# Sheet_esp32_OPTO.net
KiCad netlist of a schematic drawn in Altium Designer
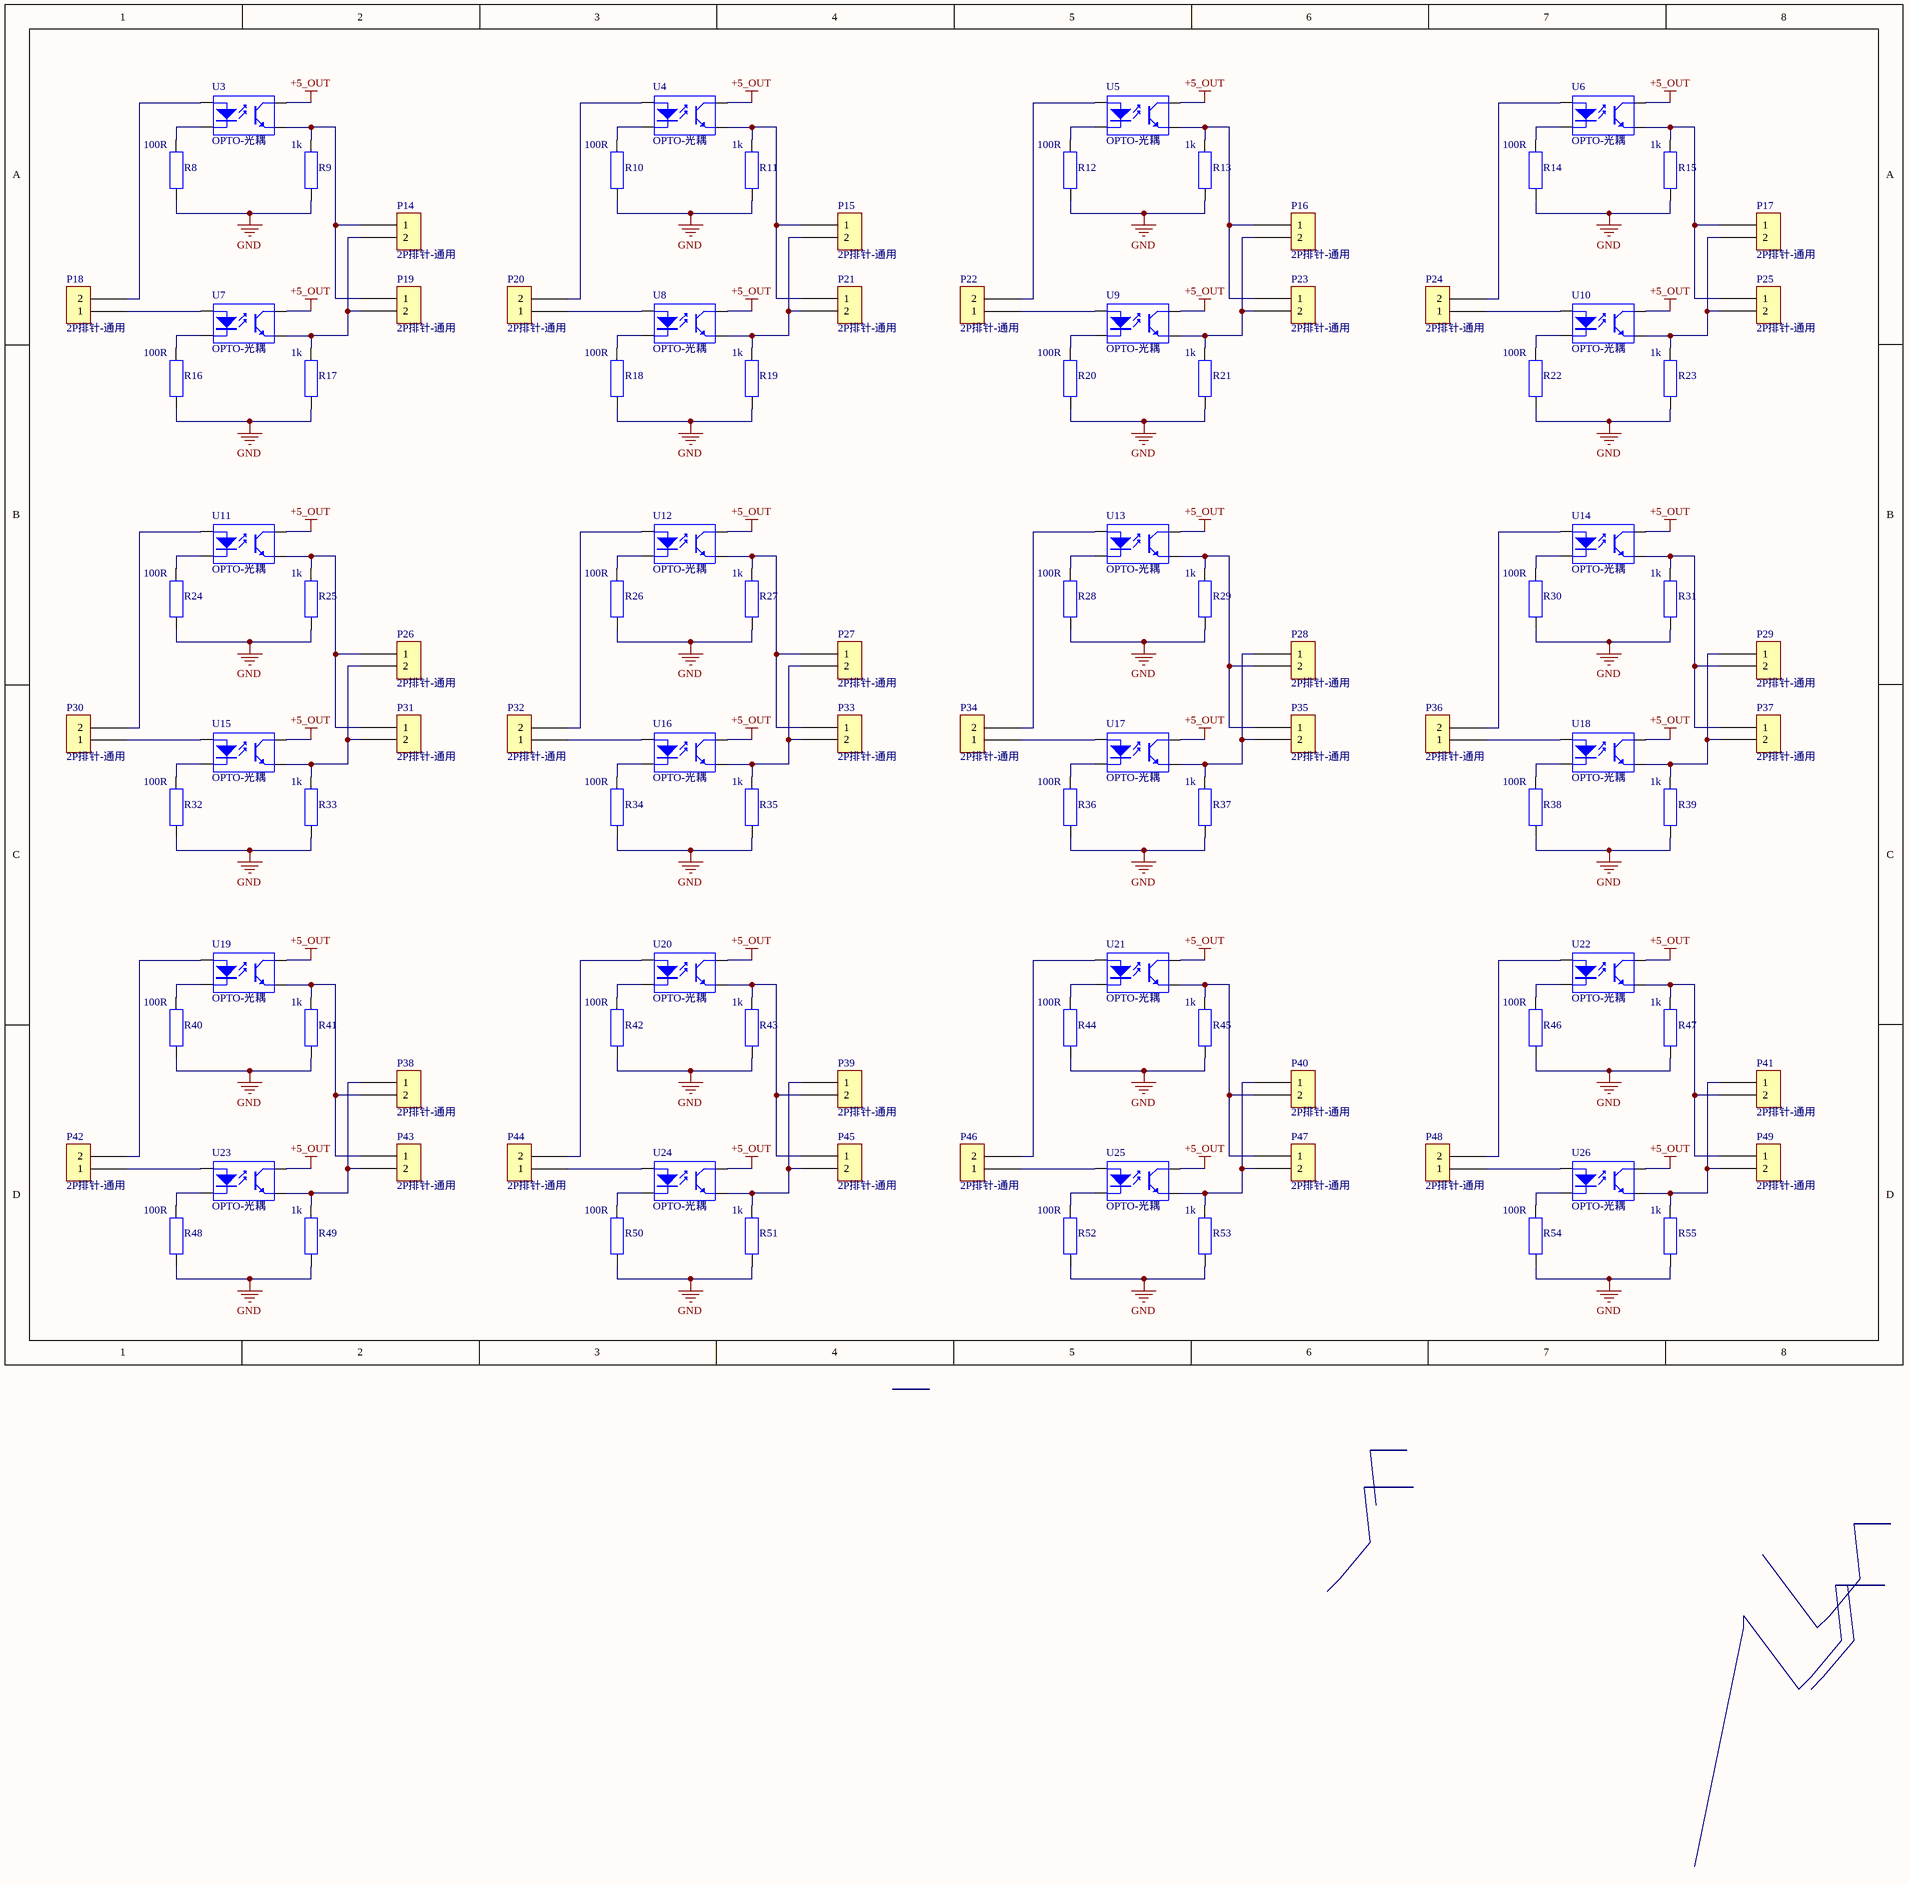
[diagram p0: Sheet_esp32_OPTO.SchDoc]

(export (version "E")
  (design (tool "Eeschema 10.0.6"))
  (components
    (comp (ref "P14")
      (value "2P排针-通用")
      (footprint "2P-KF2EDGK插头")
      (fields (field (name "PUBLISHER") "Altium Limited"))
      (libsource (lib "") (part "2P排针-通用_1"))
    )
    (comp (ref "P15")
      (value "2P排针-通用")
      (footprint "2P-KF2EDGK插头")
      (fields (field (name "PUBLISHER") "Altium Limited"))
      (libsource (lib "") (part "2P排针-通用_1"))
    )
    (comp (ref "P16")
      (value "2P排针-通用")
      (footprint "2P-KF2EDGK插头")
      (fields (field (name "PUBLISHER") "Altium Limited"))
      (libsource (lib "") (part "2P排针-通用_1"))
    )
    (comp (ref "P17")
      (value "2P排针-通用")
      (footprint "2P-KF2EDGK插头")
      (fields (field (name "PUBLISHER") "Altium Limited"))
      (libsource (lib "") (part "2P排针-通用_1"))
    )
    (comp (ref "P18")
      (value "2P排针-通用")
      (footprint "2p排针-通用")
      (fields (field (name "PUBLISHER") "Altium Limited"))
      (libsource (lib "Him_原理图库") (part "2P排针-通用"))
    )
    (comp (ref "P19")
      (value "2P排针-通用")
      (footprint "2p排针-通用")
      (fields (field (name "PUBLISHER") "Altium Limited"))
      (libsource (lib "") (part "2P排针-通用_1"))
    )
    (comp (ref "P20")
      (value "2P排针-通用")
      (footprint "2p排针-通用")
      (fields (field (name "PUBLISHER") "Altium Limited"))
      (libsource (lib "Him_原理图库") (part "2P排针-通用"))
    )
    (comp (ref "P21")
      (value "2P排针-通用")
      (footprint "2p排针-通用")
      (fields (field (name "PUBLISHER") "Altium Limited"))
      (libsource (lib "") (part "2P排针-通用_1"))
    )
    (comp (ref "P22")
      (value "2P排针-通用")
      (footprint "2p排针-通用")
      (fields (field (name "PUBLISHER") "Altium Limited"))
      (libsource (lib "Him_原理图库") (part "2P排针-通用"))
    )
    (comp (ref "P23")
      (value "2P排针-通用")
      (footprint "2p排针-通用")
      (fields (field (name "PUBLISHER") "Altium Limited"))
      (libsource (lib "") (part "2P排针-通用_1"))
    )
    (comp (ref "P24")
      (value "2P排针-通用")
      (footprint "2p排针-通用")
      (fields (field (name "PUBLISHER") "Altium Limited"))
      (libsource (lib "Him_原理图库") (part "2P排针-通用"))
    )
    (comp (ref "P25")
      (value "2P排针-通用")
      (footprint "2p排针-通用")
      (fields (field (name "PUBLISHER") "Altium Limited"))
      (libsource (lib "") (part "2P排针-通用_1"))
    )
    (comp (ref "P26")
      (value "2P排针-通用")
      (footprint "2P-KF2EDGK插头")
      (fields (field (name "PUBLISHER") "Altium Limited"))
      (libsource (lib "") (part "2P排针-通用_1"))
    )
    (comp (ref "P27")
      (value "2P排针-通用")
      (footprint "2P-KF2EDGK插头")
      (fields (field (name "PUBLISHER") "Altium Limited"))
      (libsource (lib "") (part "2P排针-通用_1"))
    )
    (comp (ref "P28")
      (value "2P排针-通用")
      (footprint "2P-KF2EDGK插头")
      (fields (field (name "PUBLISHER") "Altium Limited"))
      (libsource (lib "") (part "2P排针-通用_1"))
    )
    (comp (ref "P29")
      (value "2P排针-通用")
      (footprint "2P-KF2EDGK插头")
      (fields (field (name "PUBLISHER") "Altium Limited"))
      (libsource (lib "") (part "2P排针-通用_1"))
    )
    (comp (ref "P30")
      (value "2P排针-通用")
      (footprint "2p排针-通用")
      (fields (field (name "PUBLISHER") "Altium Limited"))
      (libsource (lib "Him_原理图库") (part "2P排针-通用"))
    )
    (comp (ref "P31")
      (value "2P排针-通用")
      (footprint "2p排针-通用")
      (fields (field (name "PUBLISHER") "Altium Limited"))
      (libsource (lib "") (part "2P排针-通用_1"))
    )
    (comp (ref "P32")
      (value "2P排针-通用")
      (footprint "2p排针-通用")
      (fields (field (name "PUBLISHER") "Altium Limited"))
      (libsource (lib "Him_原理图库") (part "2P排针-通用"))
    )
    (comp (ref "P33")
      (value "2P排针-通用")
      (footprint "2p排针-通用")
      (fields (field (name "PUBLISHER") "Altium Limited"))
      (libsource (lib "") (part "2P排针-通用_1"))
    )
    (comp (ref "P34")
      (value "2P排针-通用")
      (footprint "2p排针-通用")
      (fields (field (name "PUBLISHER") "Altium Limited"))
      (libsource (lib "Him_原理图库") (part "2P排针-通用"))
    )
    (comp (ref "P35")
      (value "2P排针-通用")
      (footprint "2p排针-通用")
      (fields (field (name "PUBLISHER") "Altium Limited"))
      (libsource (lib "") (part "2P排针-通用_1"))
    )
    (comp (ref "P36")
      (value "2P排针-通用")
      (footprint "2p排针-通用")
      (fields (field (name "PUBLISHER") "Altium Limited"))
      (libsource (lib "Him_原理图库") (part "2P排针-通用"))
    )
    (comp (ref "P37")
      (value "2P排针-通用")
      (footprint "2p排针-通用")
      (fields (field (name "PUBLISHER") "Altium Limited"))
      (libsource (lib "") (part "2P排针-通用_1"))
    )
    (comp (ref "P38")
      (value "2P排针-通用")
      (footprint "2P-KF2EDGK插头")
      (fields (field (name "PUBLISHER") "Altium Limited"))
      (libsource (lib "") (part "2P排针-通用_1"))
    )
    (comp (ref "P39")
      (value "2P排针-通用")
      (footprint "2P-KF2EDGK插头")
      (fields (field (name "PUBLISHER") "Altium Limited"))
      (libsource (lib "") (part "2P排针-通用_1"))
    )
    (comp (ref "P40")
      (value "2P排针-通用")
      (footprint "2P-KF2EDGK插头")
      (fields (field (name "PUBLISHER") "Altium Limited"))
      (libsource (lib "") (part "2P排针-通用_1"))
    )
    (comp (ref "P41")
      (value "2P排针-通用")
      (footprint "2P-KF2EDGK插头")
      (fields (field (name "PUBLISHER") "Altium Limited"))
      (libsource (lib "") (part "2P排针-通用_1"))
    )
    (comp (ref "P42")
      (value "2P排针-通用")
      (footprint "2p排针-通用")
      (fields (field (name "PUBLISHER") "Altium Limited"))
      (libsource (lib "Him_原理图库") (part "2P排针-通用"))
    )
    (comp (ref "P43")
      (value "2P排针-通用")
      (footprint "2p排针-通用")
      (fields (field (name "PUBLISHER") "Altium Limited"))
      (libsource (lib "") (part "2P排针-通用_1"))
    )
    (comp (ref "P44")
      (value "2P排针-通用")
      (footprint "2p排针-通用")
      (fields (field (name "PUBLISHER") "Altium Limited"))
      (libsource (lib "Him_原理图库") (part "2P排针-通用"))
    )
    (comp (ref "P45")
      (value "2P排针-通用")
      (footprint "2p排针-通用")
      (fields (field (name "PUBLISHER") "Altium Limited"))
      (libsource (lib "") (part "2P排针-通用_1"))
    )
    (comp (ref "P46")
      (value "2P排针-通用")
      (footprint "2p排针-通用")
      (fields (field (name "PUBLISHER") "Altium Limited"))
      (libsource (lib "Him_原理图库") (part "2P排针-通用"))
    )
    (comp (ref "P47")
      (value "2P排针-通用")
      (footprint "2p排针-通用")
      (fields (field (name "PUBLISHER") "Altium Limited"))
      (libsource (lib "") (part "2P排针-通用_1"))
    )
    (comp (ref "P48")
      (value "2P排针-通用")
      (footprint "2p排针-通用")
      (fields (field (name "PUBLISHER") "Altium Limited"))
      (libsource (lib "Him_原理图库") (part "2P排针-通用"))
    )
    (comp (ref "P49")
      (value "2P排针-通用")
      (footprint "2p排针-通用")
      (fields (field (name "PUBLISHER") "Altium Limited"))
      (libsource (lib "") (part "2P排针-通用_1"))
    )
    (comp (ref "R8")
      (value "100R")
      (footprint "贴片0805-手工")
      (description "Resistor")
      (fields (field (name "PUBLISHER") "Altium Limited"))
      (libsource (lib "Him_原理图库") (part "电阻 - 通用"))
    )
    (comp (ref "R9")
      (value "1k")
      (footprint "贴片0805-手工")
      (description "Resistor")
      (fields (field (name "PUBLISHER") "Altium Limited"))
      (libsource (lib "Him_原理图库") (part "电阻 - 通用"))
    )
    (comp (ref "R10")
      (value "100R")
      (footprint "贴片0805-手工")
      (description "Resistor")
      (fields (field (name "PUBLISHER") "Altium Limited"))
      (libsource (lib "Him_原理图库") (part "电阻 - 通用"))
    )
    (comp (ref "R11")
      (value "1k")
      (footprint "贴片0805-手工")
      (description "Resistor")
      (fields (field (name "PUBLISHER") "Altium Limited"))
      (libsource (lib "Him_原理图库") (part "电阻 - 通用"))
    )
    (comp (ref "R12")
      (value "100R")
      (footprint "贴片0805-手工")
      (description "Resistor")
      (fields (field (name "PUBLISHER") "Altium Limited"))
      (libsource (lib "Him_原理图库") (part "电阻 - 通用"))
    )
    (comp (ref "R13")
      (value "1k")
      (footprint "贴片0805-手工")
      (description "Resistor")
      (fields (field (name "PUBLISHER") "Altium Limited"))
      (libsource (lib "Him_原理图库") (part "电阻 - 通用"))
    )
    (comp (ref "R14")
      (value "100R")
      (footprint "贴片0805-手工")
      (description "Resistor")
      (fields (field (name "PUBLISHER") "Altium Limited"))
      (libsource (lib "Him_原理图库") (part "电阻 - 通用"))
    )
    (comp (ref "R15")
      (value "1k")
      (footprint "贴片0805-手工")
      (description "Resistor")
      (fields (field (name "PUBLISHER") "Altium Limited"))
      (libsource (lib "Him_原理图库") (part "电阻 - 通用"))
    )
    (comp (ref "R16")
      (value "100R")
      (footprint "贴片0805-手工")
      (description "Resistor")
      (fields (field (name "PUBLISHER") "Altium Limited"))
      (libsource (lib "Him_原理图库") (part "电阻 - 通用"))
    )
    (comp (ref "R17")
      (value "1k")
      (footprint "贴片0805-手工")
      (description "Resistor")
      (fields (field (name "PUBLISHER") "Altium Limited"))
      (libsource (lib "Him_原理图库") (part "电阻 - 通用"))
    )
    (comp (ref "R18")
      (value "100R")
      (footprint "贴片0805-手工")
      (description "Resistor")
      (fields (field (name "PUBLISHER") "Altium Limited"))
      (libsource (lib "Him_原理图库") (part "电阻 - 通用"))
    )
    (comp (ref "R19")
      (value "1k")
      (footprint "贴片0805-手工")
      (description "Resistor")
      (fields (field (name "PUBLISHER") "Altium Limited"))
      (libsource (lib "Him_原理图库") (part "电阻 - 通用"))
    )
    (comp (ref "R20")
      (value "100R")
      (footprint "贴片0805-手工")
      (description "Resistor")
      (fields (field (name "PUBLISHER") "Altium Limited"))
      (libsource (lib "Him_原理图库") (part "电阻 - 通用"))
    )
    (comp (ref "R21")
      (value "1k")
      (footprint "贴片0805-手工")
      (description "Resistor")
      (fields (field (name "PUBLISHER") "Altium Limited"))
      (libsource (lib "Him_原理图库") (part "电阻 - 通用"))
    )
    (comp (ref "R22")
      (value "100R")
      (footprint "贴片0805-手工")
      (description "Resistor")
      (fields (field (name "PUBLISHER") "Altium Limited"))
      (libsource (lib "Him_原理图库") (part "电阻 - 通用"))
    )
    (comp (ref "R23")
      (value "1k")
      (footprint "贴片0805-手工")
      (description "Resistor")
      (fields (field (name "PUBLISHER") "Altium Limited"))
      (libsource (lib "Him_原理图库") (part "电阻 - 通用"))
    )
    (comp (ref "R24")
      (value "100R")
      (footprint "贴片0805-手工")
      (description "Resistor")
      (fields (field (name "PUBLISHER") "Altium Limited"))
      (libsource (lib "Him_原理图库") (part "电阻 - 通用"))
    )
    (comp (ref "R25")
      (value "1k")
      (footprint "贴片0805-手工")
      (description "Resistor")
      (fields (field (name "PUBLISHER") "Altium Limited"))
      (libsource (lib "Him_原理图库") (part "电阻 - 通用"))
    )
    (comp (ref "R26")
      (value "100R")
      (footprint "贴片0805-手工")
      (description "Resistor")
      (fields (field (name "PUBLISHER") "Altium Limited"))
      (libsource (lib "Him_原理图库") (part "电阻 - 通用"))
    )
    (comp (ref "R27")
      (value "1k")
      (footprint "贴片0805-手工")
      (description "Resistor")
      (fields (field (name "PUBLISHER") "Altium Limited"))
      (libsource (lib "Him_原理图库") (part "电阻 - 通用"))
    )
    (comp (ref "R28")
      (value "100R")
      (footprint "贴片0805-手工")
      (description "Resistor")
      (fields (field (name "PUBLISHER") "Altium Limited"))
      (libsource (lib "Him_原理图库") (part "电阻 - 通用"))
    )
    (comp (ref "R29")
      (value "1k")
      (footprint "贴片0805-手工")
      (description "Resistor")
      (fields (field (name "PUBLISHER") "Altium Limited"))
      (libsource (lib "Him_原理图库") (part "电阻 - 通用"))
    )
    (comp (ref "R30")
      (value "100R")
      (footprint "贴片0805-手工")
      (description "Resistor")
      (fields (field (name "PUBLISHER") "Altium Limited"))
      (libsource (lib "Him_原理图库") (part "电阻 - 通用"))
    )
    (comp (ref "R31")
      (value "1k")
      (footprint "贴片0805-手工")
      (description "Resistor")
      (fields (field (name "PUBLISHER") "Altium Limited"))
      (libsource (lib "Him_原理图库") (part "电阻 - 通用"))
    )
    (comp (ref "R32")
      (value "100R")
      (footprint "贴片0805-手工")
      (description "Resistor")
      (fields (field (name "PUBLISHER") "Altium Limited"))
      (libsource (lib "Him_原理图库") (part "电阻 - 通用"))
    )
    (comp (ref "R33")
      (value "1k")
      (footprint "贴片0805-手工")
      (description "Resistor")
      (fields (field (name "PUBLISHER") "Altium Limited"))
      (libsource (lib "Him_原理图库") (part "电阻 - 通用"))
    )
    (comp (ref "R34")
      (value "100R")
      (footprint "贴片0805-手工")
      (description "Resistor")
      (fields (field (name "PUBLISHER") "Altium Limited"))
      (libsource (lib "Him_原理图库") (part "电阻 - 通用"))
    )
    (comp (ref "R35")
      (value "1k")
      (footprint "贴片0805-手工")
      (description "Resistor")
      (fields (field (name "PUBLISHER") "Altium Limited"))
      (libsource (lib "Him_原理图库") (part "电阻 - 通用"))
    )
    (comp (ref "R36")
      (value "100R")
      (footprint "贴片0805-手工")
      (description "Resistor")
      (fields (field (name "PUBLISHER") "Altium Limited"))
      (libsource (lib "Him_原理图库") (part "电阻 - 通用"))
    )
    (comp (ref "R37")
      (value "1k")
      (footprint "贴片0805-手工")
      (description "Resistor")
      (fields (field (name "PUBLISHER") "Altium Limited"))
      (libsource (lib "Him_原理图库") (part "电阻 - 通用"))
    )
    (comp (ref "R38")
      (value "100R")
      (footprint "贴片0805-手工")
      (description "Resistor")
      (fields (field (name "PUBLISHER") "Altium Limited"))
      (libsource (lib "Him_原理图库") (part "电阻 - 通用"))
    )
    (comp (ref "R39")
      (value "1k")
      (footprint "贴片0805-手工")
      (description "Resistor")
      (fields (field (name "PUBLISHER") "Altium Limited"))
      (libsource (lib "Him_原理图库") (part "电阻 - 通用"))
    )
    (comp (ref "R40")
      (value "100R")
      (footprint "贴片0805-手工")
      (description "Resistor")
      (fields (field (name "PUBLISHER") "Altium Limited"))
      (libsource (lib "Him_原理图库") (part "电阻 - 通用"))
    )
    (comp (ref "R41")
      (value "1k")
      (footprint "贴片0805-手工")
      (description "Resistor")
      (fields (field (name "PUBLISHER") "Altium Limited"))
      (libsource (lib "Him_原理图库") (part "电阻 - 通用"))
    )
    (comp (ref "R42")
      (value "100R")
      (footprint "贴片0805-手工")
      (description "Resistor")
      (fields (field (name "PUBLISHER") "Altium Limited"))
      (libsource (lib "Him_原理图库") (part "电阻 - 通用"))
    )
    (comp (ref "R43")
      (value "1k")
      (footprint "贴片0805-手工")
      (description "Resistor")
      (fields (field (name "PUBLISHER") "Altium Limited"))
      (libsource (lib "Him_原理图库") (part "电阻 - 通用"))
    )
    (comp (ref "R44")
      (value "100R")
      (footprint "贴片0805-手工")
      (description "Resistor")
      (fields (field (name "PUBLISHER") "Altium Limited"))
      (libsource (lib "Him_原理图库") (part "电阻 - 通用"))
    )
    (comp (ref "R45")
      (value "1k")
      (footprint "贴片0805-手工")
      (description "Resistor")
      (fields (field (name "PUBLISHER") "Altium Limited"))
      (libsource (lib "Him_原理图库") (part "电阻 - 通用"))
    )
    (comp (ref "R46")
      (value "100R")
      (footprint "贴片0805-手工")
      (description "Resistor")
      (fields (field (name "PUBLISHER") "Altium Limited"))
      (libsource (lib "Him_原理图库") (part "电阻 - 通用"))
    )
    (comp (ref "R47")
      (value "1k")
      (footprint "贴片0805-手工")
      (description "Resistor")
      (fields (field (name "PUBLISHER") "Altium Limited"))
      (libsource (lib "Him_原理图库") (part "电阻 - 通用"))
    )
    (comp (ref "R48")
      (value "100R")
      (footprint "贴片0805-手工")
      (description "Resistor")
      (fields (field (name "PUBLISHER") "Altium Limited"))
      (libsource (lib "Him_原理图库") (part "电阻 - 通用"))
    )
    (comp (ref "R49")
      (value "1k")
      (footprint "贴片0805-手工")
      (description "Resistor")
      (fields (field (name "PUBLISHER") "Altium Limited"))
      (libsource (lib "Him_原理图库") (part "电阻 - 通用"))
    )
    (comp (ref "R50")
      (value "100R")
      (footprint "贴片0805-手工")
      (description "Resistor")
      (fields (field (name "PUBLISHER") "Altium Limited"))
      (libsource (lib "Him_原理图库") (part "电阻 - 通用"))
    )
    (comp (ref "R51")
      (value "1k")
      (footprint "贴片0805-手工")
      (description "Resistor")
      (fields (field (name "PUBLISHER") "Altium Limited"))
      (libsource (lib "Him_原理图库") (part "电阻 - 通用"))
    )
    (comp (ref "R52")
      (value "100R")
      (footprint "贴片0805-手工")
      (description "Resistor")
      (fields (field (name "PUBLISHER") "Altium Limited"))
      (libsource (lib "Him_原理图库") (part "电阻 - 通用"))
    )
    (comp (ref "R53")
      (value "1k")
      (footprint "贴片0805-手工")
      (description "Resistor")
      (fields (field (name "PUBLISHER") "Altium Limited"))
      (libsource (lib "Him_原理图库") (part "电阻 - 通用"))
    )
    (comp (ref "R54")
      (value "100R")
      (footprint "贴片0805-手工")
      (description "Resistor")
      (fields (field (name "PUBLISHER") "Altium Limited"))
      (libsource (lib "Him_原理图库") (part "电阻 - 通用"))
    )
    (comp (ref "R55")
      (value "1k")
      (footprint "贴片0805-手工")
      (description "Resistor")
      (fields (field (name "PUBLISHER") "Altium Limited"))
      (libsource (lib "Him_原理图库") (part "电阻 - 通用"))
    )
    (comp (ref "U3")
      (value "OPTO-光耦")
      (footprint "光耦直插")
      (description "Optoisolator")
      (libsource (lib "Him_原理图库") (part "OPTO-光耦"))
    )
    (comp (ref "U4")
      (value "OPTO-光耦")
      (footprint "光耦直插")
      (description "Optoisolator")
      (libsource (lib "Him_原理图库") (part "OPTO-光耦"))
    )
    (comp (ref "U5")
      (value "OPTO-光耦")
      (footprint "光耦直插")
      (description "Optoisolator")
      (libsource (lib "Him_原理图库") (part "OPTO-光耦"))
    )
    (comp (ref "U6")
      (value "OPTO-光耦")
      (footprint "光耦直插")
      (description "Optoisolator")
      (libsource (lib "Him_原理图库") (part "OPTO-光耦"))
    )
    (comp (ref "U7")
      (value "OPTO-光耦")
      (footprint "光耦直插")
      (description "Optoisolator")
      (libsource (lib "Him_原理图库") (part "OPTO-光耦"))
    )
    (comp (ref "U8")
      (value "OPTO-光耦")
      (footprint "光耦直插")
      (description "Optoisolator")
      (libsource (lib "Him_原理图库") (part "OPTO-光耦"))
    )
    (comp (ref "U9")
      (value "OPTO-光耦")
      (footprint "光耦直插")
      (description "Optoisolator")
      (libsource (lib "Him_原理图库") (part "OPTO-光耦"))
    )
    (comp (ref "U10")
      (value "OPTO-光耦")
      (footprint "光耦直插")
      (description "Optoisolator")
      (libsource (lib "Him_原理图库") (part "OPTO-光耦"))
    )
    (comp (ref "U11")
      (value "OPTO-光耦")
      (footprint "光耦直插")
      (description "Optoisolator")
      (libsource (lib "Him_原理图库") (part "OPTO-光耦"))
    )
    (comp (ref "U12")
      (value "OPTO-光耦")
      (footprint "光耦直插")
      (description "Optoisolator")
      (libsource (lib "Him_原理图库") (part "OPTO-光耦"))
    )
    (comp (ref "U13")
      (value "OPTO-光耦")
      (footprint "光耦直插")
      (description "Optoisolator")
      (libsource (lib "Him_原理图库") (part "OPTO-光耦"))
    )
    (comp (ref "U14")
      (value "OPTO-光耦")
      (footprint "光耦直插")
      (description "Optoisolator")
      (libsource (lib "Him_原理图库") (part "OPTO-光耦"))
    )
    (comp (ref "U15")
      (value "OPTO-光耦")
      (footprint "光耦直插")
      (description "Optoisolator")
      (libsource (lib "Him_原理图库") (part "OPTO-光耦"))
    )
    (comp (ref "U16")
      (value "OPTO-光耦")
      (footprint "光耦直插")
      (description "Optoisolator")
      (libsource (lib "Him_原理图库") (part "OPTO-光耦"))
    )
    (comp (ref "U17")
      (value "OPTO-光耦")
      (footprint "光耦直插")
      (description "Optoisolator")
      (libsource (lib "Him_原理图库") (part "OPTO-光耦"))
    )
    (comp (ref "U18")
      (value "OPTO-光耦")
      (footprint "光耦直插")
      (description "Optoisolator")
      (libsource (lib "Him_原理图库") (part "OPTO-光耦"))
    )
    (comp (ref "U19")
      (value "OPTO-光耦")
      (footprint "光耦直插")
      (description "Optoisolator")
      (libsource (lib "Him_原理图库") (part "OPTO-光耦"))
    )
    (comp (ref "U20")
      (value "OPTO-光耦")
      (footprint "光耦直插")
      (description "Optoisolator")
      (libsource (lib "Him_原理图库") (part "OPTO-光耦"))
    )
    (comp (ref "U21")
      (value "OPTO-光耦")
      (footprint "光耦直插")
      (description "Optoisolator")
      (libsource (lib "Him_原理图库") (part "OPTO-光耦"))
    )
    (comp (ref "U22")
      (value "OPTO-光耦")
      (footprint "光耦直插")
      (description "Optoisolator")
      (libsource (lib "Him_原理图库") (part "OPTO-光耦"))
    )
    (comp (ref "U23")
      (value "OPTO-光耦")
      (footprint "光耦直插")
      (description "Optoisolator")
      (libsource (lib "Him_原理图库") (part "OPTO-光耦"))
    )
    (comp (ref "U24")
      (value "OPTO-光耦")
      (footprint "光耦直插")
      (description "Optoisolator")
      (libsource (lib "Him_原理图库") (part "OPTO-光耦"))
    )
    (comp (ref "U25")
      (value "OPTO-光耦")
      (footprint "光耦直插")
      (description "Optoisolator")
      (libsource (lib "Him_原理图库") (part "OPTO-光耦"))
    )
    (comp (ref "U26")
      (value "OPTO-光耦")
      (footprint "光耦直插")
      (description "Optoisolator")
      (libsource (lib "Him_原理图库") (part "OPTO-光耦"))
    )
  )
  (nets
    (net (code "1") (name "+5_OUT") (class "Default")
      (node (ref "U10") (pin "4") (pinfunction "C_4") (pintype "passive"))
      (node (ref "U11") (pin "4") (pinfunction "C_4") (pintype "passive"))
      (node (ref "U12") (pin "4") (pinfunction "C_4") (pintype "passive"))
      (node (ref "U13") (pin "4") (pinfunction "C_4") (pintype "passive"))
      (node (ref "U14") (pin "4") (pinfunction "C_4") (pintype "passive"))
      (node (ref "U15") (pin "4") (pinfunction "C_4") (pintype "passive"))
      (node (ref "U16") (pin "4") (pinfunction "C_4") (pintype "passive"))
      (node (ref "U17") (pin "4") (pinfunction "C_4") (pintype "passive"))
      (node (ref "U18") (pin "4") (pinfunction "C_4") (pintype "passive"))
      (node (ref "U19") (pin "4") (pinfunction "C_4") (pintype "passive"))
      (node (ref "U20") (pin "4") (pinfunction "C_4") (pintype "passive"))
      (node (ref "U21") (pin "4") (pinfunction "C_4") (pintype "passive"))
      (node (ref "U22") (pin "4") (pinfunction "C_4") (pintype "passive"))
      (node (ref "U23") (pin "4") (pinfunction "C_4") (pintype "passive"))
      (node (ref "U24") (pin "4") (pinfunction "C_4") (pintype "passive"))
      (node (ref "U25") (pin "4") (pinfunction "C_4") (pintype "passive"))
      (node (ref "U26") (pin "4") (pinfunction "C_4") (pintype "passive"))
      (node (ref "U3") (pin "4") (pinfunction "C_4") (pintype "passive"))
      (node (ref "U4") (pin "4") (pinfunction "C_4") (pintype "passive"))
      (node (ref "U5") (pin "4") (pinfunction "C_4") (pintype "passive"))
      (node (ref "U6") (pin "4") (pinfunction "C_4") (pintype "passive"))
      (node (ref "U7") (pin "4") (pinfunction "C_4") (pintype "passive"))
      (node (ref "U8") (pin "4") (pinfunction "C_4") (pintype "passive"))
      (node (ref "U9") (pin "4") (pinfunction "C_4") (pintype "passive"))
    )
    (net (code "2") (name "GND") (class "Default")
      (node (ref "R10") (pin "1") (pinfunction "1_1") (pintype "passive"))
      (node (ref "R11") (pin "1") (pinfunction "1_1") (pintype "passive"))
      (node (ref "R12") (pin "1") (pinfunction "1_1") (pintype "passive"))
      (node (ref "R13") (pin "1") (pinfunction "1_1") (pintype "passive"))
      (node (ref "R14") (pin "1") (pinfunction "1_1") (pintype "passive"))
      (node (ref "R15") (pin "1") (pinfunction "1_1") (pintype "passive"))
      (node (ref "R16") (pin "1") (pinfunction "1_1") (pintype "passive"))
      (node (ref "R17") (pin "1") (pinfunction "1_1") (pintype "passive"))
      (node (ref "R18") (pin "1") (pinfunction "1_1") (pintype "passive"))
      (node (ref "R19") (pin "1") (pinfunction "1_1") (pintype "passive"))
      (node (ref "R20") (pin "1") (pinfunction "1_1") (pintype "passive"))
      (node (ref "R21") (pin "1") (pinfunction "1_1") (pintype "passive"))
      (node (ref "R22") (pin "1") (pinfunction "1_1") (pintype "passive"))
      (node (ref "R23") (pin "1") (pinfunction "1_1") (pintype "passive"))
      (node (ref "R24") (pin "1") (pinfunction "1_1") (pintype "passive"))
      (node (ref "R25") (pin "1") (pinfunction "1_1") (pintype "passive"))
      (node (ref "R26") (pin "1") (pinfunction "1_1") (pintype "passive"))
      (node (ref "R27") (pin "1") (pinfunction "1_1") (pintype "passive"))
      (node (ref "R28") (pin "1") (pinfunction "1_1") (pintype "passive"))
      (node (ref "R29") (pin "1") (pinfunction "1_1") (pintype "passive"))
      (node (ref "R30") (pin "1") (pinfunction "1_1") (pintype "passive"))
      (node (ref "R31") (pin "1") (pinfunction "1_1") (pintype "passive"))
      (node (ref "R32") (pin "1") (pinfunction "1_1") (pintype "passive"))
      (node (ref "R33") (pin "1") (pinfunction "1_1") (pintype "passive"))
      (node (ref "R34") (pin "1") (pinfunction "1_1") (pintype "passive"))
      (node (ref "R35") (pin "1") (pinfunction "1_1") (pintype "passive"))
      (node (ref "R36") (pin "1") (pinfunction "1_1") (pintype "passive"))
      (node (ref "R37") (pin "1") (pinfunction "1_1") (pintype "passive"))
      (node (ref "R38") (pin "1") (pinfunction "1_1") (pintype "passive"))
      (node (ref "R39") (pin "1") (pinfunction "1_1") (pintype "passive"))
      (node (ref "R40") (pin "1") (pinfunction "1_1") (pintype "passive"))
      (node (ref "R41") (pin "1") (pinfunction "1_1") (pintype "passive"))
      (node (ref "R42") (pin "1") (pinfunction "1_1") (pintype "passive"))
      (node (ref "R43") (pin "1") (pinfunction "1_1") (pintype "passive"))
      (node (ref "R44") (pin "1") (pinfunction "1_1") (pintype "passive"))
      (node (ref "R45") (pin "1") (pinfunction "1_1") (pintype "passive"))
      (node (ref "R46") (pin "1") (pinfunction "1_1") (pintype "passive"))
      (node (ref "R47") (pin "1") (pinfunction "1_1") (pintype "passive"))
      (node (ref "R48") (pin "1") (pinfunction "1_1") (pintype "passive"))
      (node (ref "R49") (pin "1") (pinfunction "1_1") (pintype "passive"))
      (node (ref "R50") (pin "1") (pinfunction "1_1") (pintype "passive"))
      (node (ref "R51") (pin "1") (pinfunction "1_1") (pintype "passive"))
      (node (ref "R52") (pin "1") (pinfunction "1_1") (pintype "passive"))
      (node (ref "R53") (pin "1") (pinfunction "1_1") (pintype "passive"))
      (node (ref "R54") (pin "1") (pinfunction "1_1") (pintype "passive"))
      (node (ref "R55") (pin "1") (pinfunction "1_1") (pintype "passive"))
      (node (ref "R8") (pin "1") (pinfunction "1_1") (pintype "passive"))
      (node (ref "R9") (pin "1") (pinfunction "1_1") (pintype "passive"))
    )
    (net (code "3") (name "Net-(U3-A)") (class "Default")
      (node (ref "P18") (pin "2") (pinfunction "2_2") (pintype "passive"))
      (node (ref "U3") (pin "1") (pinfunction "A_1") (pintype "passive"))
    )
    (net (code "4") (name "Net-(U3-E)") (class "Default")
      (node (ref "P14") (pin "1") (pinfunction "1_1") (pintype "passive"))
      (node (ref "P19") (pin "1") (pinfunction "1_1") (pintype "passive"))
      (node (ref "R9") (pin "2") (pinfunction "2_2") (pintype "passive"))
      (node (ref "U3") (pin "3") (pinfunction "E_3") (pintype "passive"))
    )
    (net (code "5") (name "Net-(U3-K)") (class "Default")
      (node (ref "R8") (pin "2") (pinfunction "2_2") (pintype "passive"))
      (node (ref "U3") (pin "2") (pinfunction "K_2") (pintype "passive"))
    )
    (net (code "6") (name "Net-(U4-A)") (class "Default")
      (node (ref "P20") (pin "2") (pinfunction "2_2") (pintype "passive"))
      (node (ref "U4") (pin "1") (pinfunction "A_1") (pintype "passive"))
    )
    (net (code "7") (name "Net-(U4-E)") (class "Default")
      (node (ref "P15") (pin "1") (pinfunction "1_1") (pintype "passive"))
      (node (ref "P21") (pin "1") (pinfunction "1_1") (pintype "passive"))
      (node (ref "R11") (pin "2") (pinfunction "2_2") (pintype "passive"))
      (node (ref "U4") (pin "3") (pinfunction "E_3") (pintype "passive"))
    )
    (net (code "8") (name "Net-(U4-K)") (class "Default")
      (node (ref "R10") (pin "2") (pinfunction "2_2") (pintype "passive"))
      (node (ref "U4") (pin "2") (pinfunction "K_2") (pintype "passive"))
    )
    (net (code "9") (name "Net-(U5-A)") (class "Default")
      (node (ref "P22") (pin "2") (pinfunction "2_2") (pintype "passive"))
      (node (ref "U5") (pin "1") (pinfunction "A_1") (pintype "passive"))
    )
    (net (code "10") (name "Net-(U5-E)") (class "Default")
      (node (ref "P16") (pin "1") (pinfunction "1_1") (pintype "passive"))
      (node (ref "P23") (pin "1") (pinfunction "1_1") (pintype "passive"))
      (node (ref "R13") (pin "2") (pinfunction "2_2") (pintype "passive"))
      (node (ref "U5") (pin "3") (pinfunction "E_3") (pintype "passive"))
    )
    (net (code "11") (name "Net-(U5-K)") (class "Default")
      (node (ref "R12") (pin "2") (pinfunction "2_2") (pintype "passive"))
      (node (ref "U5") (pin "2") (pinfunction "K_2") (pintype "passive"))
    )
    (net (code "12") (name "Net-(U6-A)") (class "Default")
      (node (ref "P24") (pin "2") (pinfunction "2_2") (pintype "passive"))
      (node (ref "U6") (pin "1") (pinfunction "A_1") (pintype "passive"))
    )
    (net (code "13") (name "Net-(U6-E)") (class "Default")
      (node (ref "P17") (pin "1") (pinfunction "1_1") (pintype "passive"))
      (node (ref "P25") (pin "1") (pinfunction "1_1") (pintype "passive"))
      (node (ref "R15") (pin "2") (pinfunction "2_2") (pintype "passive"))
      (node (ref "U6") (pin "3") (pinfunction "E_3") (pintype "passive"))
    )
    (net (code "14") (name "Net-(U6-K)") (class "Default")
      (node (ref "R14") (pin "2") (pinfunction "2_2") (pintype "passive"))
      (node (ref "U6") (pin "2") (pinfunction "K_2") (pintype "passive"))
    )
    (net (code "15") (name "Net-(U7-A)") (class "Default")
      (node (ref "P18") (pin "1") (pinfunction "1_1") (pintype "passive"))
      (node (ref "U7") (pin "1") (pinfunction "A_1") (pintype "passive"))
    )
    (net (code "16") (name "Net-(U7-E)") (class "Default")
      (node (ref "P14") (pin "2") (pinfunction "2_2") (pintype "passive"))
      (node (ref "P19") (pin "2") (pinfunction "2_2") (pintype "passive"))
      (node (ref "R17") (pin "2") (pinfunction "2_2") (pintype "passive"))
      (node (ref "U7") (pin "3") (pinfunction "E_3") (pintype "passive"))
    )
    (net (code "17") (name "Net-(U7-K)") (class "Default")
      (node (ref "R16") (pin "2") (pinfunction "2_2") (pintype "passive"))
      (node (ref "U7") (pin "2") (pinfunction "K_2") (pintype "passive"))
    )
    (net (code "18") (name "Net-(U8-A)") (class "Default")
      (node (ref "P20") (pin "1") (pinfunction "1_1") (pintype "passive"))
      (node (ref "U8") (pin "1") (pinfunction "A_1") (pintype "passive"))
    )
    (net (code "19") (name "Net-(U8-E)") (class "Default")
      (node (ref "P15") (pin "2") (pinfunction "2_2") (pintype "passive"))
      (node (ref "P21") (pin "2") (pinfunction "2_2") (pintype "passive"))
      (node (ref "R19") (pin "2") (pinfunction "2_2") (pintype "passive"))
      (node (ref "U8") (pin "3") (pinfunction "E_3") (pintype "passive"))
    )
    (net (code "20") (name "Net-(U8-K)") (class "Default")
      (node (ref "R18") (pin "2") (pinfunction "2_2") (pintype "passive"))
      (node (ref "U8") (pin "2") (pinfunction "K_2") (pintype "passive"))
    )
    (net (code "21") (name "Net-(U9-A)") (class "Default")
      (node (ref "P22") (pin "1") (pinfunction "1_1") (pintype "passive"))
      (node (ref "U9") (pin "1") (pinfunction "A_1") (pintype "passive"))
    )
    (net (code "22") (name "Net-(U9-E)") (class "Default")
      (node (ref "P16") (pin "2") (pinfunction "2_2") (pintype "passive"))
      (node (ref "P23") (pin "2") (pinfunction "2_2") (pintype "passive"))
      (node (ref "R21") (pin "2") (pinfunction "2_2") (pintype "passive"))
      (node (ref "U9") (pin "3") (pinfunction "E_3") (pintype "passive"))
    )
    (net (code "23") (name "Net-(U9-K)") (class "Default")
      (node (ref "R20") (pin "2") (pinfunction "2_2") (pintype "passive"))
      (node (ref "U9") (pin "2") (pinfunction "K_2") (pintype "passive"))
    )
    (net (code "24") (name "Net-(U10-A)") (class "Default")
      (node (ref "P24") (pin "1") (pinfunction "1_1") (pintype "passive"))
      (node (ref "U10") (pin "1") (pinfunction "A_1") (pintype "passive"))
    )
    (net (code "25") (name "Net-(U10-E)") (class "Default")
      (node (ref "P17") (pin "2") (pinfunction "2_2") (pintype "passive"))
      (node (ref "P25") (pin "2") (pinfunction "2_2") (pintype "passive"))
      (node (ref "R23") (pin "2") (pinfunction "2_2") (pintype "passive"))
      (node (ref "U10") (pin "3") (pinfunction "E_3") (pintype "passive"))
    )
    (net (code "26") (name "Net-(U10-K)") (class "Default")
      (node (ref "R22") (pin "2") (pinfunction "2_2") (pintype "passive"))
      (node (ref "U10") (pin "2") (pinfunction "K_2") (pintype "passive"))
    )
    (net (code "27") (name "Net-(U11-A)") (class "Default")
      (node (ref "P30") (pin "2") (pinfunction "2_2") (pintype "passive"))
      (node (ref "U11") (pin "1") (pinfunction "A_1") (pintype "passive"))
    )
    (net (code "28") (name "Net-(U11-E)") (class "Default")
      (node (ref "P26") (pin "1") (pinfunction "1_1") (pintype "passive"))
      (node (ref "P31") (pin "1") (pinfunction "1_1") (pintype "passive"))
      (node (ref "R25") (pin "2") (pinfunction "2_2") (pintype "passive"))
      (node (ref "U11") (pin "3") (pinfunction "E_3") (pintype "passive"))
    )
    (net (code "29") (name "Net-(U11-K)") (class "Default")
      (node (ref "R24") (pin "2") (pinfunction "2_2") (pintype "passive"))
      (node (ref "U11") (pin "2") (pinfunction "K_2") (pintype "passive"))
    )
    (net (code "30") (name "Net-(U12-A)") (class "Default")
      (node (ref "P32") (pin "2") (pinfunction "2_2") (pintype "passive"))
      (node (ref "U12") (pin "1") (pinfunction "A_1") (pintype "passive"))
    )
    (net (code "31") (name "Net-(U12-E)") (class "Default")
      (node (ref "P27") (pin "1") (pinfunction "1_1") (pintype "passive"))
      (node (ref "P33") (pin "1") (pinfunction "1_1") (pintype "passive"))
      (node (ref "R27") (pin "2") (pinfunction "2_2") (pintype "passive"))
      (node (ref "U12") (pin "3") (pinfunction "E_3") (pintype "passive"))
    )
    (net (code "32") (name "Net-(U12-K)") (class "Default")
      (node (ref "R26") (pin "2") (pinfunction "2_2") (pintype "passive"))
      (node (ref "U12") (pin "2") (pinfunction "K_2") (pintype "passive"))
    )
    (net (code "33") (name "Net-(U13-A)") (class "Default")
      (node (ref "P34") (pin "2") (pinfunction "2_2") (pintype "passive"))
      (node (ref "U13") (pin "1") (pinfunction "A_1") (pintype "passive"))
    )
    (net (code "34") (name "Net-(U13-E)") (class "Default")
      (node (ref "P28") (pin "2") (pinfunction "2_2") (pintype "passive"))
      (node (ref "P35") (pin "1") (pinfunction "1_1") (pintype "passive"))
      (node (ref "R29") (pin "2") (pinfunction "2_2") (pintype "passive"))
      (node (ref "U13") (pin "3") (pinfunction "E_3") (pintype "passive"))
    )
    (net (code "35") (name "Net-(U13-K)") (class "Default")
      (node (ref "R28") (pin "2") (pinfunction "2_2") (pintype "passive"))
      (node (ref "U13") (pin "2") (pinfunction "K_2") (pintype "passive"))
    )
    (net (code "36") (name "Net-(U14-A)") (class "Default")
      (node (ref "P36") (pin "2") (pinfunction "2_2") (pintype "passive"))
      (node (ref "U14") (pin "1") (pinfunction "A_1") (pintype "passive"))
    )
    (net (code "37") (name "Net-(U14-E)") (class "Default")
      (node (ref "P29") (pin "2") (pinfunction "2_2") (pintype "passive"))
      (node (ref "P37") (pin "1") (pinfunction "1_1") (pintype "passive"))
      (node (ref "R31") (pin "2") (pinfunction "2_2") (pintype "passive"))
      (node (ref "U14") (pin "3") (pinfunction "E_3") (pintype "passive"))
    )
    (net (code "38") (name "Net-(U14-K)") (class "Default")
      (node (ref "R30") (pin "2") (pinfunction "2_2") (pintype "passive"))
      (node (ref "U14") (pin "2") (pinfunction "K_2") (pintype "passive"))
    )
    (net (code "39") (name "Net-(U15-A)") (class "Default")
      (node (ref "P30") (pin "1") (pinfunction "1_1") (pintype "passive"))
      (node (ref "U15") (pin "1") (pinfunction "A_1") (pintype "passive"))
    )
    (net (code "40") (name "Net-(U15-E)") (class "Default")
      (node (ref "P26") (pin "2") (pinfunction "2_2") (pintype "passive"))
      (node (ref "P31") (pin "2") (pinfunction "2_2") (pintype "passive"))
      (node (ref "R33") (pin "2") (pinfunction "2_2") (pintype "passive"))
      (node (ref "U15") (pin "3") (pinfunction "E_3") (pintype "passive"))
    )
    (net (code "41") (name "Net-(U15-K)") (class "Default")
      (node (ref "R32") (pin "2") (pinfunction "2_2") (pintype "passive"))
      (node (ref "U15") (pin "2") (pinfunction "K_2") (pintype "passive"))
    )
    (net (code "42") (name "Net-(U16-A)") (class "Default")
      (node (ref "P32") (pin "1") (pinfunction "1_1") (pintype "passive"))
      (node (ref "U16") (pin "1") (pinfunction "A_1") (pintype "passive"))
    )
    (net (code "43") (name "Net-(U16-E)") (class "Default")
      (node (ref "P27") (pin "2") (pinfunction "2_2") (pintype "passive"))
      (node (ref "P33") (pin "2") (pinfunction "2_2") (pintype "passive"))
      (node (ref "R35") (pin "2") (pinfunction "2_2") (pintype "passive"))
      (node (ref "U16") (pin "3") (pinfunction "E_3") (pintype "passive"))
    )
    (net (code "44") (name "Net-(U16-K)") (class "Default")
      (node (ref "R34") (pin "2") (pinfunction "2_2") (pintype "passive"))
      (node (ref "U16") (pin "2") (pinfunction "K_2") (pintype "passive"))
    )
    (net (code "45") (name "Net-(U17-A)") (class "Default")
      (node (ref "P34") (pin "1") (pinfunction "1_1") (pintype "passive"))
      (node (ref "U17") (pin "1") (pinfunction "A_1") (pintype "passive"))
    )
    (net (code "46") (name "Net-(U17-E)") (class "Default")
      (node (ref "P28") (pin "1") (pinfunction "1_1") (pintype "passive"))
      (node (ref "P35") (pin "2") (pinfunction "2_2") (pintype "passive"))
      (node (ref "R37") (pin "2") (pinfunction "2_2") (pintype "passive"))
      (node (ref "U17") (pin "3") (pinfunction "E_3") (pintype "passive"))
    )
    (net (code "47") (name "Net-(U17-K)") (class "Default")
      (node (ref "R36") (pin "2") (pinfunction "2_2") (pintype "passive"))
      (node (ref "U17") (pin "2") (pinfunction "K_2") (pintype "passive"))
    )
    (net (code "48") (name "Net-(U18-A)") (class "Default")
      (node (ref "P36") (pin "1") (pinfunction "1_1") (pintype "passive"))
      (node (ref "U18") (pin "1") (pinfunction "A_1") (pintype "passive"))
    )
    (net (code "49") (name "Net-(U18-E)") (class "Default")
      (node (ref "P29") (pin "1") (pinfunction "1_1") (pintype "passive"))
      (node (ref "P37") (pin "2") (pinfunction "2_2") (pintype "passive"))
      (node (ref "R39") (pin "2") (pinfunction "2_2") (pintype "passive"))
      (node (ref "U18") (pin "3") (pinfunction "E_3") (pintype "passive"))
    )
    (net (code "50") (name "Net-(U18-K)") (class "Default")
      (node (ref "R38") (pin "2") (pinfunction "2_2") (pintype "passive"))
      (node (ref "U18") (pin "2") (pinfunction "K_2") (pintype "passive"))
    )
    (net (code "51") (name "Net-(U19-A)") (class "Default")
      (node (ref "P42") (pin "2") (pinfunction "2_2") (pintype "passive"))
      (node (ref "U19") (pin "1") (pinfunction "A_1") (pintype "passive"))
    )
    (net (code "52") (name "Net-(U19-E)") (class "Default")
      (node (ref "P38") (pin "2") (pinfunction "2_2") (pintype "passive"))
      (node (ref "P43") (pin "1") (pinfunction "1_1") (pintype "passive"))
      (node (ref "R41") (pin "2") (pinfunction "2_2") (pintype "passive"))
      (node (ref "U19") (pin "3") (pinfunction "E_3") (pintype "passive"))
    )
    (net (code "53") (name "Net-(U19-K)") (class "Default")
      (node (ref "R40") (pin "2") (pinfunction "2_2") (pintype "passive"))
      (node (ref "U19") (pin "2") (pinfunction "K_2") (pintype "passive"))
    )
    (net (code "54") (name "Net-(U20-A)") (class "Default")
      (node (ref "P44") (pin "2") (pinfunction "2_2") (pintype "passive"))
      (node (ref "U20") (pin "1") (pinfunction "A_1") (pintype "passive"))
    )
    (net (code "55") (name "Net-(U20-E)") (class "Default")
      (node (ref "P39") (pin "2") (pinfunction "2_2") (pintype "passive"))
      (node (ref "P45") (pin "1") (pinfunction "1_1") (pintype "passive"))
      (node (ref "R43") (pin "2") (pinfunction "2_2") (pintype "passive"))
      (node (ref "U20") (pin "3") (pinfunction "E_3") (pintype "passive"))
    )
    (net (code "56") (name "Net-(U20-K)") (class "Default")
      (node (ref "R42") (pin "2") (pinfunction "2_2") (pintype "passive"))
      (node (ref "U20") (pin "2") (pinfunction "K_2") (pintype "passive"))
    )
    (net (code "57") (name "Net-(U21-A)") (class "Default")
      (node (ref "P46") (pin "2") (pinfunction "2_2") (pintype "passive"))
      (node (ref "U21") (pin "1") (pinfunction "A_1") (pintype "passive"))
    )
    (net (code "58") (name "Net-(U21-E)") (class "Default")
      (node (ref "P40") (pin "2") (pinfunction "2_2") (pintype "passive"))
      (node (ref "P47") (pin "1") (pinfunction "1_1") (pintype "passive"))
      (node (ref "R45") (pin "2") (pinfunction "2_2") (pintype "passive"))
      (node (ref "U21") (pin "3") (pinfunction "E_3") (pintype "passive"))
    )
    (net (code "59") (name "Net-(U21-K)") (class "Default")
      (node (ref "R44") (pin "2") (pinfunction "2_2") (pintype "passive"))
      (node (ref "U21") (pin "2") (pinfunction "K_2") (pintype "passive"))
    )
    (net (code "60") (name "Net-(U22-A)") (class "Default")
      (node (ref "P48") (pin "2") (pinfunction "2_2") (pintype "passive"))
      (node (ref "U22") (pin "1") (pinfunction "A_1") (pintype "passive"))
    )
    (net (code "61") (name "Net-(U22-E)") (class "Default")
      (node (ref "P41") (pin "2") (pinfunction "2_2") (pintype "passive"))
      (node (ref "P49") (pin "1") (pinfunction "1_1") (pintype "passive"))
      (node (ref "R47") (pin "2") (pinfunction "2_2") (pintype "passive"))
      (node (ref "U22") (pin "3") (pinfunction "E_3") (pintype "passive"))
    )
    (net (code "62") (name "Net-(U22-K)") (class "Default")
      (node (ref "R46") (pin "2") (pinfunction "2_2") (pintype "passive"))
      (node (ref "U22") (pin "2") (pinfunction "K_2") (pintype "passive"))
    )
    (net (code "63") (name "Net-(U23-A)") (class "Default")
      (node (ref "P42") (pin "1") (pinfunction "1_1") (pintype "passive"))
      (node (ref "U23") (pin "1") (pinfunction "A_1") (pintype "passive"))
    )
    (net (code "64") (name "Net-(U23-E)") (class "Default")
      (node (ref "P38") (pin "1") (pinfunction "1_1") (pintype "passive"))
      (node (ref "P43") (pin "2") (pinfunction "2_2") (pintype "passive"))
      (node (ref "R49") (pin "2") (pinfunction "2_2") (pintype "passive"))
      (node (ref "U23") (pin "3") (pinfunction "E_3") (pintype "passive"))
    )
    (net (code "65") (name "Net-(U23-K)") (class "Default")
      (node (ref "R48") (pin "2") (pinfunction "2_2") (pintype "passive"))
      (node (ref "U23") (pin "2") (pinfunction "K_2") (pintype "passive"))
    )
    (net (code "66") (name "Net-(U24-A)") (class "Default")
      (node (ref "P44") (pin "1") (pinfunction "1_1") (pintype "passive"))
      (node (ref "U24") (pin "1") (pinfunction "A_1") (pintype "passive"))
    )
    (net (code "67") (name "Net-(U24-E)") (class "Default")
      (node (ref "P39") (pin "1") (pinfunction "1_1") (pintype "passive"))
      (node (ref "P45") (pin "2") (pinfunction "2_2") (pintype "passive"))
      (node (ref "R51") (pin "2") (pinfunction "2_2") (pintype "passive"))
      (node (ref "U24") (pin "3") (pinfunction "E_3") (pintype "passive"))
    )
    (net (code "68") (name "Net-(U24-K)") (class "Default")
      (node (ref "R50") (pin "2") (pinfunction "2_2") (pintype "passive"))
      (node (ref "U24") (pin "2") (pinfunction "K_2") (pintype "passive"))
    )
    (net (code "69") (name "Net-(U25-A)") (class "Default")
      (node (ref "P46") (pin "1") (pinfunction "1_1") (pintype "passive"))
      (node (ref "U25") (pin "1") (pinfunction "A_1") (pintype "passive"))
    )
    (net (code "70") (name "Net-(U25-E)") (class "Default")
      (node (ref "P40") (pin "1") (pinfunction "1_1") (pintype "passive"))
      (node (ref "P47") (pin "2") (pinfunction "2_2") (pintype "passive"))
      (node (ref "R53") (pin "2") (pinfunction "2_2") (pintype "passive"))
      (node (ref "U25") (pin "3") (pinfunction "E_3") (pintype "passive"))
    )
    (net (code "71") (name "Net-(U25-K)") (class "Default")
      (node (ref "R52") (pin "2") (pinfunction "2_2") (pintype "passive"))
      (node (ref "U25") (pin "2") (pinfunction "K_2") (pintype "passive"))
    )
    (net (code "72") (name "Net-(U26-A)") (class "Default")
      (node (ref "P48") (pin "1") (pinfunction "1_1") (pintype "passive"))
      (node (ref "U26") (pin "1") (pinfunction "A_1") (pintype "passive"))
    )
    (net (code "73") (name "Net-(U26-E)") (class "Default")
      (node (ref "P41") (pin "1") (pinfunction "1_1") (pintype "passive"))
      (node (ref "P49") (pin "2") (pinfunction "2_2") (pintype "passive"))
      (node (ref "R55") (pin "2") (pinfunction "2_2") (pintype "passive"))
      (node (ref "U26") (pin "3") (pinfunction "E_3") (pintype "passive"))
    )
    (net (code "74") (name "Net-(U26-K)") (class "Default")
      (node (ref "R54") (pin "2") (pinfunction "2_2") (pintype "passive"))
      (node (ref "U26") (pin "2") (pinfunction "K_2") (pintype "passive"))
    )
  )
)
